# usb_usb2534.net
KiCad netlist of a schematic drawn in Altium Designer
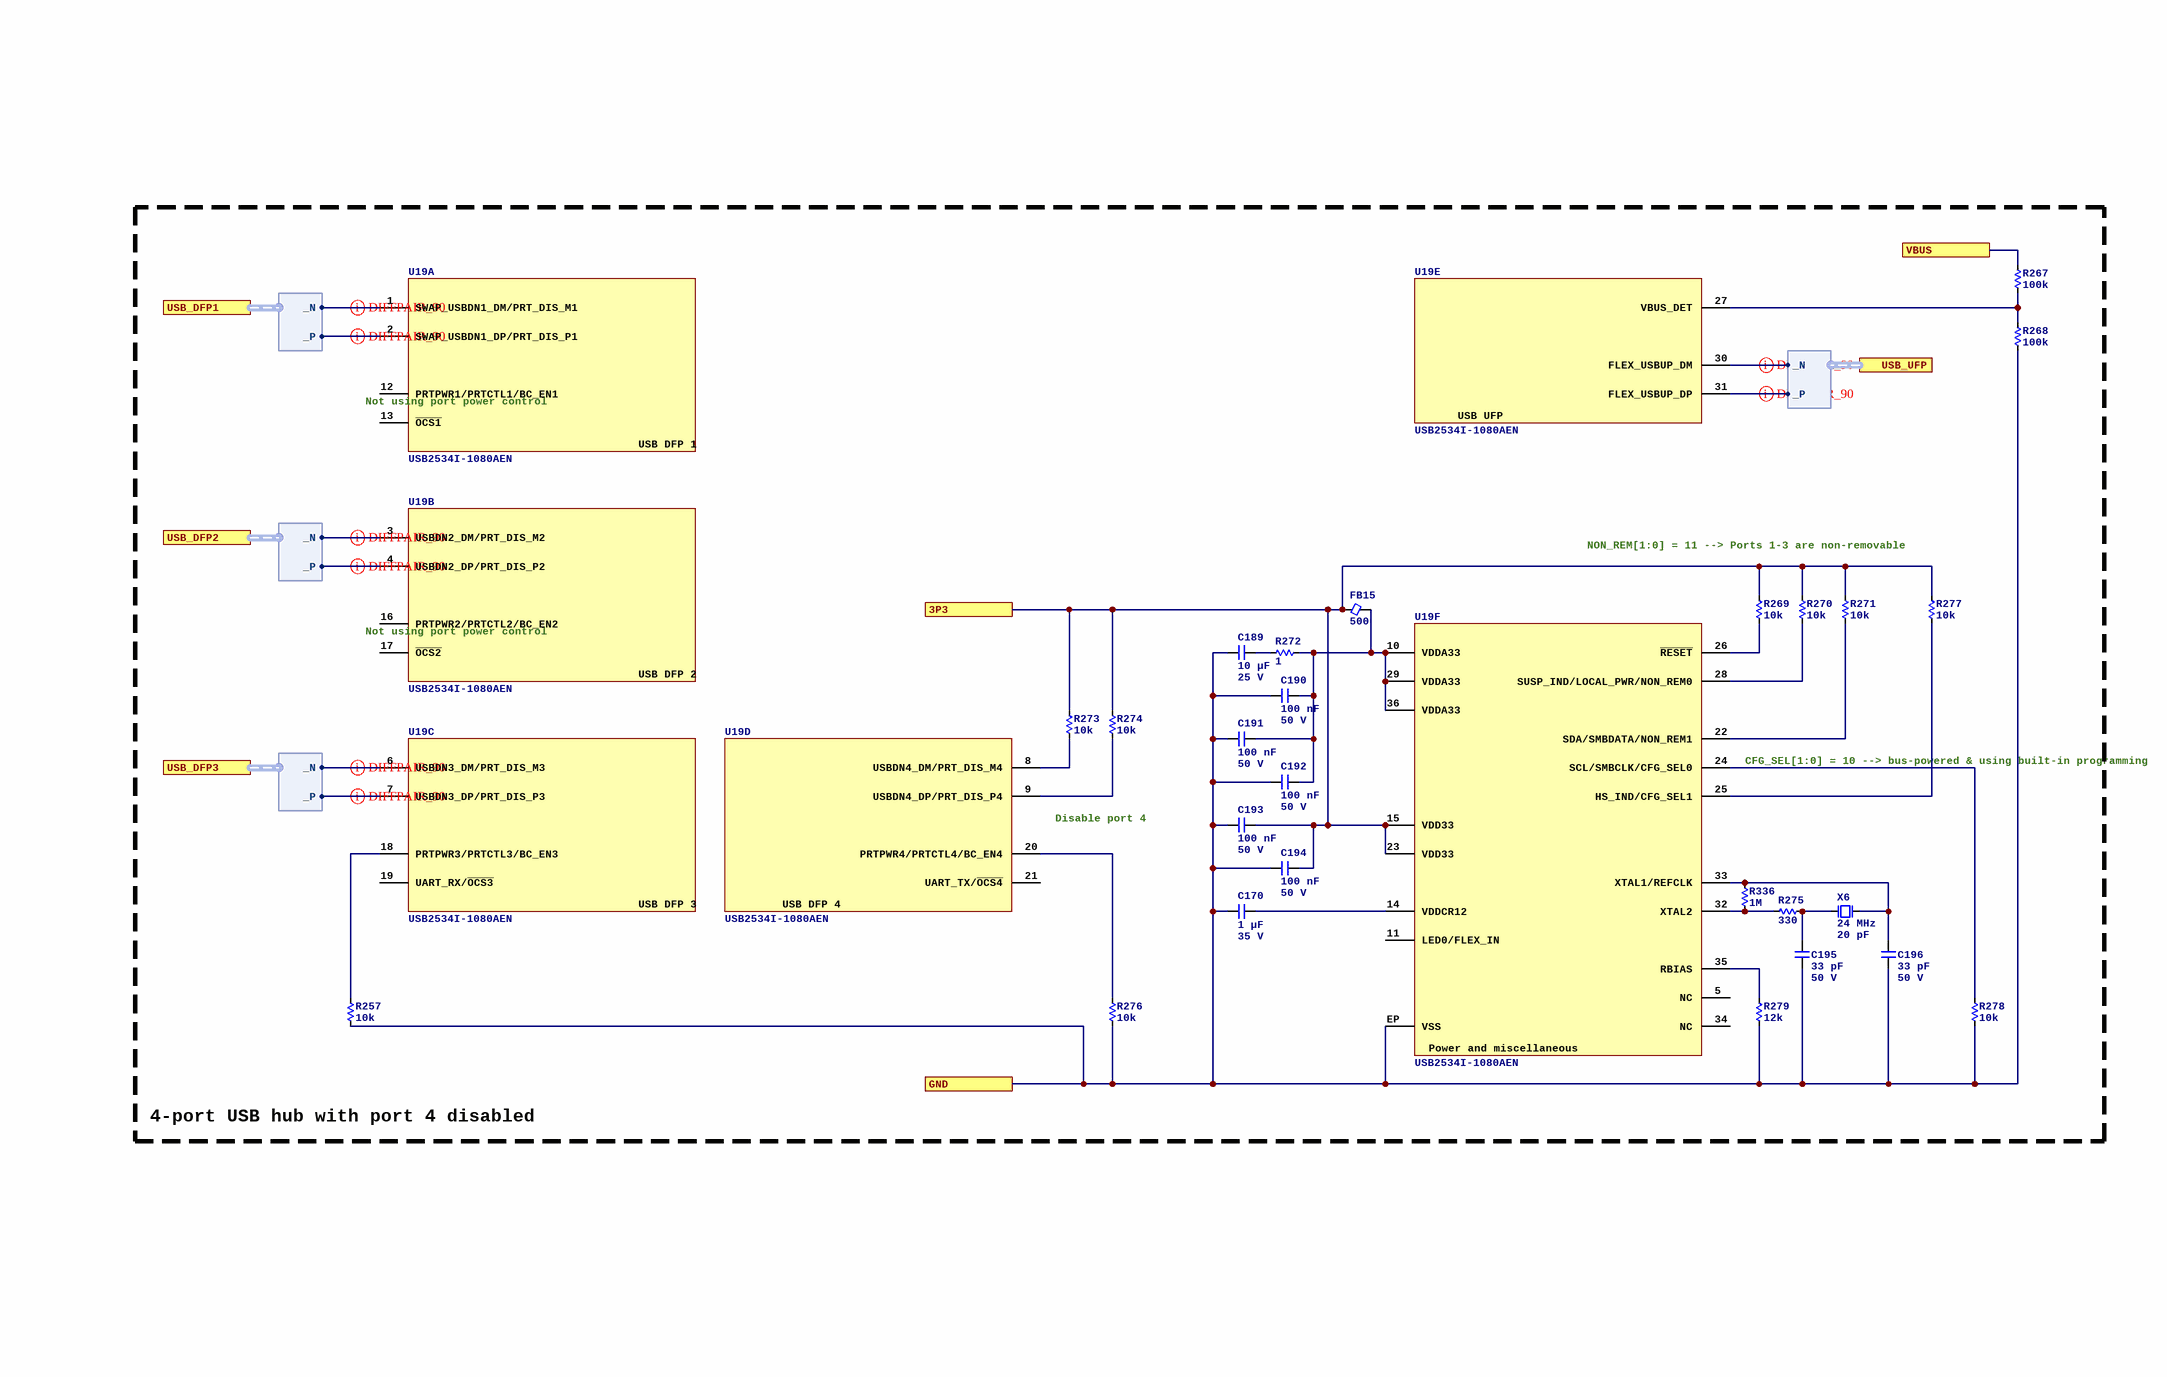
[diagram p0: usb_usb2534.SchDoc]

(export (version "E")
  (design (tool "Eeschema 10.0.6"))
  (components
    (comp (ref "C170")
      (value "GMK107AB7105KAHT")
      (footprint "C0603")
      (fields
        (field (name "CAPACITANCE") "1 µF")
        (field (name "MANUFACTURER") "Taiyo Yuden")
        (field (name "VOLTAGE RATING") "35 V")
      )
      (libsource (lib "database") (part "__template_cap"))
    )
    (comp (ref "C189")
      (value "CL21B106KAYQNNE")
      (footprint "C0805")
      (fields
        (field (name "CAPACITANCE") "10 µF")
        (field (name "MANUFACTURER") "Samsung Electro-Mechanics")
        (field (name "VOLTAGE RATING") "25 V")
      )
      (libsource (lib "database") (part "__template_cap"))
    )
    (comp (ref "C190")
      (value "CL05B104KB54PNC")
      (footprint "C0402")
      (fields
        (field (name "CAPACITANCE") "100 nF")
        (field (name "MANUFACTURER") "Samsung Electro-Mechanics")
        (field (name "VOLTAGE RATING") "50 V")
      )
      (libsource (lib "database") (part "__template_cap"))
    )
    (comp (ref "C191")
      (value "CL05B104KB54PNC")
      (footprint "C0402")
      (fields
        (field (name "CAPACITANCE") "100 nF")
        (field (name "MANUFACTURER") "Samsung Electro-Mechanics")
        (field (name "VOLTAGE RATING") "50 V")
      )
      (libsource (lib "database") (part "__template_cap"))
    )
    (comp (ref "C192")
      (value "CL05B104KB54PNC")
      (footprint "C0402")
      (fields
        (field (name "CAPACITANCE") "100 nF")
        (field (name "MANUFACTURER") "Samsung Electro-Mechanics")
        (field (name "VOLTAGE RATING") "50 V")
      )
      (libsource (lib "database") (part "__template_cap"))
    )
    (comp (ref "C193")
      (value "CL05B104KB54PNC")
      (footprint "C0402")
      (fields
        (field (name "CAPACITANCE") "100 nF")
        (field (name "MANUFACTURER") "Samsung Electro-Mechanics")
        (field (name "VOLTAGE RATING") "50 V")
      )
      (libsource (lib "database") (part "__template_cap"))
    )
    (comp (ref "C194")
      (value "CL05B104KB54PNC")
      (footprint "C0402")
      (fields
        (field (name "CAPACITANCE") "100 nF")
        (field (name "MANUFACTURER") "Samsung Electro-Mechanics")
        (field (name "VOLTAGE RATING") "50 V")
      )
      (libsource (lib "database") (part "__template_cap"))
    )
    (comp (ref "C195")
      (value "0402CG330J500NT")
      (footprint "C0402")
      (fields
        (field (name "CAPACITANCE") "33 pF")
        (field (name "MANUFACTURER") "FH(Guangdong Fenghua Advanced Tech)")
        (field (name "VOLTAGE RATING") "50 V")
      )
      (libsource (lib "database") (part "__template_cap"))
    )
    (comp (ref "C196")
      (value "0402CG330J500NT")
      (footprint "C0402")
      (fields
        (field (name "CAPACITANCE") "33 pF")
        (field (name "MANUFACTURER") "FH(Guangdong Fenghua Advanced Tech)")
        (field (name "VOLTAGE RATING") "50 V")
      )
      (libsource (lib "database") (part "__template_cap"))
    )
    (comp (ref "FB15")
      (value "BLM15AX601SN1D")
      (footprint "FB0402")
      (fields (field (name "MANUFACTURER") "Murata Electronics") (field (name "CURRENT RATING (MA)") "500"))
      (libsource (lib "database") (part "__template_fb"))
    )
    (comp (ref "R257")
      (value "10k")
      (footprint "R0402")
      (fields
        (field (name "TOLERANCE") "1%")
        (field (name "MANUFACTURER PART NUMBER") "0402WGF1002TCE")
        (field (name "MANUFACTURER") "UNI-ROYAL(Uniroyal Elec)")
      )
      (libsource (lib "database") (part "__template_resistor"))
    )
    (comp (ref "R267")
      (value "100k")
      (footprint "R0402")
      (fields
        (field (name "TOLERANCE") "1%")
        (field (name "MANUFACTURER PART NUMBER") "0402WGF1003TCE")
        (field (name "MANUFACTURER") "UNI-ROYAL(Uniroyal Elec)")
      )
      (libsource (lib "database") (part "__template_resistor"))
    )
    (comp (ref "R268")
      (value "100k")
      (footprint "R0402")
      (fields
        (field (name "TOLERANCE") "1%")
        (field (name "MANUFACTURER PART NUMBER") "0402WGF1003TCE")
        (field (name "MANUFACTURER") "UNI-ROYAL(Uniroyal Elec)")
      )
      (libsource (lib "database") (part "__template_resistor"))
    )
    (comp (ref "R269")
      (value "10k")
      (footprint "R0402")
      (fields
        (field (name "TOLERANCE") "1%")
        (field (name "MANUFACTURER PART NUMBER") "0402WGF1002TCE")
        (field (name "MANUFACTURER") "UNI-ROYAL(Uniroyal Elec)")
      )
      (libsource (lib "database") (part "__template_resistor"))
    )
    (comp (ref "R270")
      (value "10k")
      (footprint "R0402")
      (fields
        (field (name "TOLERANCE") "1%")
        (field (name "MANUFACTURER PART NUMBER") "0402WGF1002TCE")
        (field (name "MANUFACTURER") "UNI-ROYAL(Uniroyal Elec)")
      )
      (libsource (lib "database") (part "__template_resistor"))
    )
    (comp (ref "R271")
      (value "10k")
      (footprint "R0402")
      (fields
        (field (name "TOLERANCE") "1%")
        (field (name "MANUFACTURER PART NUMBER") "0402WGF1002TCE")
        (field (name "MANUFACTURER") "UNI-ROYAL(Uniroyal Elec)")
      )
      (libsource (lib "database") (part "__template_resistor"))
    )
    (comp (ref "R272")
      (value "1")
      (footprint "R0402")
      (fields
        (field (name "TOLERANCE") "1%")
        (field (name "MANUFACTURER PART NUMBER") "CRCW04021R00FKED")
        (field (name "MANUFACTURER") "Vishay Intertech")
      )
      (libsource (lib "database") (part "__template_resistor"))
    )
    (comp (ref "R273")
      (value "10k")
      (footprint "R0402")
      (fields
        (field (name "TOLERANCE") "1%")
        (field (name "MANUFACTURER PART NUMBER") "0402WGF1002TCE")
        (field (name "MANUFACTURER") "UNI-ROYAL(Uniroyal Elec)")
      )
      (libsource (lib "database") (part "__template_resistor"))
    )
    (comp (ref "R274")
      (value "10k")
      (footprint "R0402")
      (fields
        (field (name "TOLERANCE") "1%")
        (field (name "MANUFACTURER PART NUMBER") "0402WGF1002TCE")
        (field (name "MANUFACTURER") "UNI-ROYAL(Uniroyal Elec)")
      )
      (libsource (lib "database") (part "__template_resistor"))
    )
    (comp (ref "R275")
      (value "330")
      (footprint "R0402")
      (fields
        (field (name "TOLERANCE") "1%")
        (field (name "MANUFACTURER PART NUMBER") "0402WGF3300TCE")
        (field (name "MANUFACTURER") "UNI-ROYAL(Uniroyal Elec)")
      )
      (libsource (lib "database") (part "__template_resistor"))
    )
    (comp (ref "R276")
      (value "10k")
      (footprint "R0402")
      (fields
        (field (name "TOLERANCE") "1%")
        (field (name "MANUFACTURER PART NUMBER") "0402WGF1002TCE")
        (field (name "MANUFACTURER") "UNI-ROYAL(Uniroyal Elec)")
      )
      (libsource (lib "database") (part "__template_resistor"))
    )
    (comp (ref "R277")
      (value "10k")
      (footprint "R0402")
      (fields
        (field (name "TOLERANCE") "1%")
        (field (name "MANUFACTURER PART NUMBER") "0402WGF1002TCE")
        (field (name "MANUFACTURER") "UNI-ROYAL(Uniroyal Elec)")
      )
      (libsource (lib "database") (part "__template_resistor"))
    )
    (comp (ref "R278")
      (value "10k")
      (footprint "R0402")
      (fields
        (field (name "TOLERANCE") "1%")
        (field (name "MANUFACTURER PART NUMBER") "0402WGF1002TCE")
        (field (name "MANUFACTURER") "UNI-ROYAL(Uniroyal Elec)")
      )
      (libsource (lib "database") (part "__template_resistor"))
    )
    (comp (ref "R279")
      (value "12k")
      (footprint "R0402")
      (fields
        (field (name "TOLERANCE") "1%")
        (field (name "MANUFACTURER PART NUMBER") "0402WGF1202TCE")
        (field (name "MANUFACTURER") "UNI-ROYAL(Uniroyal Elec)")
      )
      (libsource (lib "database") (part "__template_resistor"))
    )
    (comp (ref "R336")
      (value "1M")
      (footprint "R0402")
      (fields
        (field (name "TOLERANCE") "1%")
        (field (name "MANUFACTURER PART NUMBER") "0402WGF1004TCE")
        (field (name "MANUFACTURER") "UNI-ROYAL(Uniroyal Elec)")
      )
      (libsource (lib "database") (part "__template_resistor"))
    )
    (comp (ref "U19")
      (value "USB2534I-1080AEN")
      (footprint "QFN50P600X600X90-36N")
      (description "USB Bus Controller, CMOS")
      (fields (field (name "MANUFACTURER") "Microchip"))
      (libsource (lib "database") (part "USB2534I-1080AEN"))
    )
    (comp (ref "X6")
      (value "TAXM24M2QLFCDT1T")
      (footprint "XTAL_TXC_7A")
      (description "CRYSTAL 24.000 MHZ 20PF SMD")
      (fields
        (field (name "FREQUENCY") "24 MHz")
        (field (name "MANUFACTURER") "Yajingxin")
        (field (name "CAPACITANCE") "20 pF")
      )
      (libsource (lib "database") (part "__template_crystal_2pin"))
    )
  )
  (nets
    (net (code "2") (name "/3P3") (class "Default")
      (node (ref "C193") (pin "1") (pintype "passive"))
      (node (ref "C194") (pin "1") (pintype "passive"))
      (node (ref "FB15") (pin "1") (pintype "passive"))
      (node (ref "R269") (pin "1") (pintype "passive"))
      (node (ref "R270") (pin "1") (pintype "passive"))
      (node (ref "R271") (pin "1") (pintype "passive"))
      (node (ref "R273") (pin "1") (pintype "passive"))
      (node (ref "R274") (pin "1") (pintype "passive"))
      (node (ref "R277") (pin "1") (pintype "passive"))
      (node (ref "U19") (pin "15") (pinfunction "VDD33_15") (pintype "passive"))
      (node (ref "U19") (pin "23") (pinfunction "VDD33_23") (pintype "passive"))
    )
    (net (code "3") (name "/GND") (class "Default")
      (node (ref "C170") (pin "2") (pintype "passive"))
      (node (ref "C189") (pin "2") (pintype "passive"))
      (node (ref "C190") (pin "2") (pintype "passive"))
      (node (ref "C191") (pin "2") (pintype "passive"))
      (node (ref "C192") (pin "2") (pintype "passive"))
      (node (ref "C193") (pin "2") (pintype "passive"))
      (node (ref "C194") (pin "2") (pintype "passive"))
      (node (ref "C195") (pin "2") (pintype "passive"))
      (node (ref "C196") (pin "2") (pintype "passive"))
      (node (ref "R257") (pin "2") (pintype "passive"))
      (node (ref "R268") (pin "1") (pintype "passive"))
      (node (ref "R276") (pin "2") (pintype "passive"))
      (node (ref "R278") (pin "2") (pintype "passive"))
      (node (ref "R279") (pin "2") (pintype "passive"))
      (node (ref "U19") (pin "EP") (pinfunction "VSS_EP") (pintype "passive"))
    )
    (net (code "4") (name "/VBUS") (class "Default") (node (ref "R267") (pin "1") (pintype "passive")))
    (net (code "6") (name "Net-(C189-Pad1)") (class "Default")
      (node (ref "C189") (pin "1") (pintype "passive"))
      (node (ref "R272") (pin "2") (pintype "passive"))
    )
    (net (code "7") (name "Net-(C190-Pad1)") (class "Default")
      (node (ref "C190") (pin "1") (pintype "passive"))
      (node (ref "C191") (pin "1") (pintype "passive"))
      (node (ref "C192") (pin "1") (pintype "passive"))
      (node (ref "FB15") (pin "2") (pintype "passive"))
      (node (ref "R272") (pin "1") (pintype "passive"))
      (node (ref "U19") (pin "10") (pinfunction "VDDA33_10") (pintype "passive"))
      (node (ref "U19") (pin "29") (pinfunction "VDDA33_29") (pintype "passive"))
      (node (ref "U19") (pin "36") (pinfunction "VDDA33_36") (pintype "passive"))
    )
    (net (code "8") (name "Net-(C195-Pad1)") (class "Default")
      (node (ref "C195") (pin "1") (pintype "passive"))
      (node (ref "R275") (pin "1") (pintype "passive"))
      (node (ref "X6") (pin "1") (pinfunction "1_1") (pintype "passive"))
    )
    (net (code "9") (name "Net-(U19C-PRTPWR3{slash}PRTCTL3{slash}BC_EN3)") (class "Default")
      (node (ref "R257") (pin "1") (pintype "passive"))
      (node (ref "U19") (pin "18") (pinfunction "PRTPWR3/PRTCTL3/BC_EN3_18") (pintype "passive"))
    )
    (net (code "10") (name "Net-(U19D-PRTPWR4{slash}PRTCTL4{slash}BC_EN4)") (class "Default")
      (node (ref "R276") (pin "1") (pintype "passive"))
      (node (ref "U19") (pin "20") (pinfunction "PRTPWR4/PRTCTL4/BC_EN4_20") (pintype "passive"))
    )
    (net (code "11") (name "Net-(U19D-USBDN4_DM{slash}PRT_DIS_M4)") (class "Default")
      (node (ref "R273") (pin "2") (pintype "passive"))
      (node (ref "U19") (pin "8") (pinfunction "USBDN4_DM/PRT_DIS_M4_8") (pintype "passive"))
    )
    (net (code "12") (name "Net-(U19D-USBDN4_DP{slash}PRT_DIS_P4)") (class "Default")
      (node (ref "R274") (pin "2") (pintype "passive"))
      (node (ref "U19") (pin "9") (pinfunction "USBDN4_DP/PRT_DIS_P4_9") (pintype "passive"))
    )
    (net (code "13") (name "Net-(U19E-VBUS_DET)") (class "Default")
      (node (ref "R267") (pin "2") (pintype "passive"))
      (node (ref "R268") (pin "2") (pintype "passive"))
      (node (ref "U19") (pin "27") (pinfunction "VBUS_DET_27") (pintype "passive"))
    )
    (net (code "14") (name "Net-(U19F-HS_IND{slash}CFG_SEL1)") (class "Default")
      (node (ref "R277") (pin "2") (pintype "passive"))
      (node (ref "U19") (pin "25") (pinfunction "HS_IND/CFG_SEL1_25") (pintype "passive"))
    )
    (net (code "15") (name "Net-(U19F-RBIAS)") (class "Default")
      (node (ref "R279") (pin "1") (pintype "passive"))
      (node (ref "U19") (pin "35") (pinfunction "RBIAS_35") (pintype "passive"))
    )
    (net (code "16") (name "Net-(U19F-SCL{slash}SMBCLK{slash}CFG_SEL0)") (class "Default")
      (node (ref "R278") (pin "1") (pintype "passive"))
      (node (ref "U19") (pin "24") (pinfunction "SCL/SMBCLK/CFG_SEL0_24") (pintype "passive"))
    )
    (net (code "17") (name "Net-(U19F-SDA{slash}SMBDATA{slash}NON_REM1)") (class "Default")
      (node (ref "R271") (pin "2") (pintype "passive"))
      (node (ref "U19") (pin "22") (pinfunction "SDA/SMBDATA/NON_REM1_22") (pintype "passive"))
    )
    (net (code "18") (name "Net-(U19F-SUSP_IND{slash}LOCAL_PWR{slash}NON_REM0)") (class "Default")
      (node (ref "R270") (pin "2") (pintype "passive"))
      (node (ref "U19") (pin "28") (pinfunction "SUSP_IND/LOCAL_PWR/NON_REM0_28") (pintype "passive"))
    )
    (net (code "19") (name "Net-(U19F-VDDCR12)") (class "Default")
      (node (ref "C170") (pin "1") (pintype "passive"))
      (node (ref "U19") (pin "14") (pinfunction "VDDCR12_14") (pintype "passive"))
    )
    (net (code "20") (name "Net-(U19F-XTAL1{slash}REFCLK)") (class "Default")
      (node (ref "C196") (pin "1") (pintype "passive"))
      (node (ref "R336") (pin "1") (pintype "passive"))
      (node (ref "U19") (pin "33") (pinfunction "XTAL1/REFCLK_33") (pintype "passive"))
      (node (ref "X6") (pin "2") (pinfunction "2_2") (pintype "passive"))
    )
    (net (code "21") (name "Net-(U19F-XTAL2)") (class "Default")
      (node (ref "R275") (pin "2") (pintype "passive"))
      (node (ref "R336") (pin "2") (pintype "passive"))
      (node (ref "U19") (pin "32") (pinfunction "XTAL2_32") (pintype "passive"))
    )
    (net (code "22") (name "Net-(U19F-~{RESET})") (class "Default")
      (node (ref "R269") (pin "2") (pintype "passive"))
      (node (ref "U19") (pin "26") (pinfunction "~{RESET}_26") (pintype "passive"))
    )
    (net (code "23") (name "unconnected-(U19A-PRTPWR1{slash}PRTCTL1{slash}BC_EN1-Pad12)") (class "Default")
      (node (ref "U19") (pin "12") (pinfunction "PRTPWR1/PRTCTL1/BC_EN1_12") (pintype "passive"))
    )
    (net (code "24") (name "unconnected-(U19A-SWAP_USBDN1_DM{slash}PRT_DIS_M1-Pad1)") (class "Default")
      (node (ref "U19") (pin "1") (pinfunction "SWAP_USBDN1_DM/PRT_DIS_M1_1") (pintype "passive"))
    )
    (net (code "25") (name "unconnected-(U19A-SWAP_USBDN1_DP{slash}PRT_DIS_P1-Pad2)") (class "Default")
      (node (ref "U19") (pin "2") (pinfunction "SWAP_USBDN1_DP/PRT_DIS_P1_2") (pintype "passive"))
    )
    (net (code "26") (name "unconnected-(U19A-~{OCS1}-Pad13)") (class "Default")
      (node (ref "U19") (pin "13") (pinfunction "~{OCS1}_13") (pintype "passive"))
    )
    (net (code "27") (name "unconnected-(U19B-PRTPWR2{slash}PRTCTL2{slash}BC_EN2-Pad16)") (class "Default")
      (node (ref "U19") (pin "16") (pinfunction "PRTPWR2/PRTCTL2/BC_EN2_16") (pintype "passive"))
    )
    (net (code "28") (name "unconnected-(U19B-USBDN2_DM{slash}PRT_DIS_M2-Pad3)") (class "Default")
      (node (ref "U19") (pin "3") (pinfunction "USBDN2_DM/PRT_DIS_M2_3") (pintype "passive"))
    )
    (net (code "29") (name "unconnected-(U19B-USBDN2_DP{slash}PRT_DIS_P2-Pad4)") (class "Default")
      (node (ref "U19") (pin "4") (pinfunction "USBDN2_DP/PRT_DIS_P2_4") (pintype "passive"))
    )
    (net (code "30") (name "unconnected-(U19B-~{OCS2}-Pad17)") (class "Default")
      (node (ref "U19") (pin "17") (pinfunction "~{OCS2}_17") (pintype "passive"))
    )
    (net (code "31") (name "unconnected-(U19C-UART_RX{slash}~{OCS3}-Pad19)") (class "Default")
      (node (ref "U19") (pin "19") (pinfunction "UART_RX/~{OCS3}_19") (pintype "passive"))
    )
    (net (code "32") (name "unconnected-(U19C-USBDN3_DM{slash}PRT_DIS_M3-Pad6)") (class "Default")
      (node (ref "U19") (pin "6") (pinfunction "USBDN3_DM/PRT_DIS_M3_6") (pintype "passive"))
    )
    (net (code "33") (name "unconnected-(U19C-USBDN3_DP{slash}PRT_DIS_P3-Pad7)") (class "Default")
      (node (ref "U19") (pin "7") (pinfunction "USBDN3_DP/PRT_DIS_P3_7") (pintype "passive"))
    )
    (net (code "34") (name "unconnected-(U19D-UART_TX{slash}~{OCS4}-Pad21)") (class "Default")
      (node (ref "U19") (pin "21") (pinfunction "UART_TX/~{OCS4}_21") (pintype "passive"))
    )
    (net (code "35") (name "unconnected-(U19E-FLEX_USBUP_DM-Pad30)") (class "Default")
      (node (ref "U19") (pin "30") (pinfunction "FLEX_USBUP_DM_30") (pintype "passive"))
    )
    (net (code "36") (name "unconnected-(U19E-FLEX_USBUP_DP-Pad31)") (class "Default")
      (node (ref "U19") (pin "31") (pinfunction "FLEX_USBUP_DP_31") (pintype "passive"))
    )
    (net (code "37") (name "unconnected-(U19F-LED0{slash}FLEX_IN-Pad11)") (class "Default")
      (node (ref "U19") (pin "11") (pinfunction "LED0/FLEX_IN_11") (pintype "passive"))
    )
    (net (code "38") (name "unconnected-(U19F-NC-Pad5)") (class "Default")
      (node (ref "U19") (pin "5") (pinfunction "NC_5") (pintype "passive"))
    )
    (net (code "39") (name "unconnected-(U19F-NC-Pad34)") (class "Default")
      (node (ref "U19") (pin "34") (pinfunction "NC_34") (pintype "passive"))
    )
  )
)
